# PracticalDMX.net
KiCad netlist of a schematic drawn in EAGLE
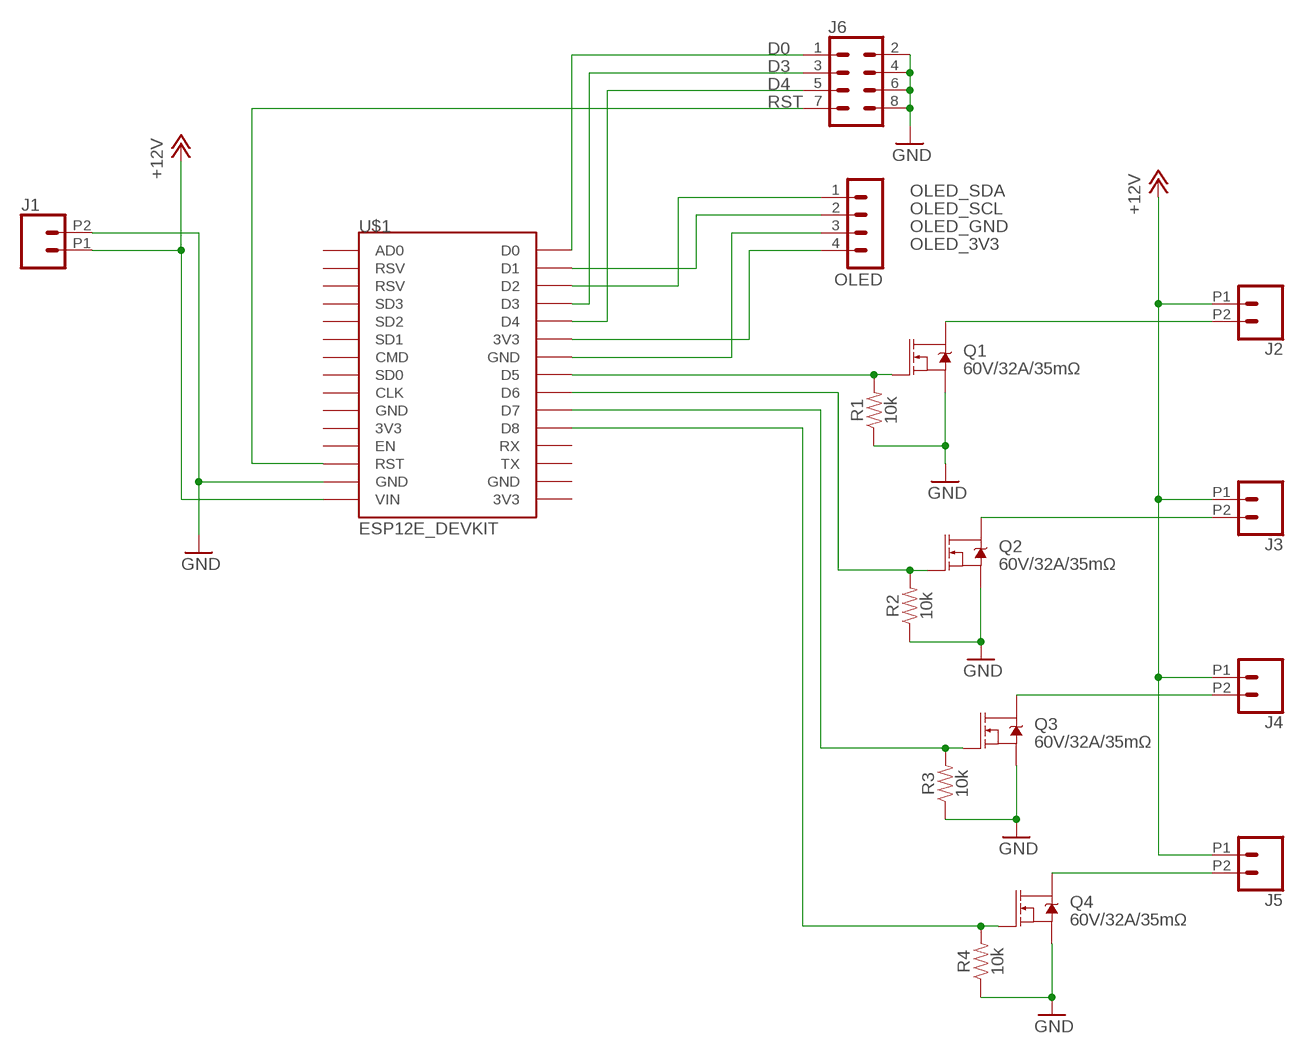
[diagram p0: schematic, sheet 1]

(export (version "E")
  (design (tool "Eeschema 10.0.6"))
  (components
    (comp (ref "J1")
      (value "CONN_022.54MM_SCREWTERM")
      (footprint "eagle-import:1X02_2.54_SCREWTERM")
      (libsource (lib "eagle-import") (part "CONN_022.54MM_SCREWTERM"))
    )
    (comp (ref "J2")
      (value "CONN_022.54MM_SCREWTERM")
      (footprint "eagle-import:1X02_2.54_SCREWTERM")
      (libsource (lib "eagle-import") (part "CONN_022.54MM_SCREWTERM"))
    )
    (comp (ref "J3")
      (value "CONN_022.54MM_SCREWTERM")
      (footprint "eagle-import:1X02_2.54_SCREWTERM")
      (libsource (lib "eagle-import") (part "CONN_022.54MM_SCREWTERM"))
    )
    (comp (ref "J4")
      (value "CONN_022.54MM_SCREWTERM")
      (footprint "eagle-import:1X02_2.54_SCREWTERM")
      (libsource (lib "eagle-import") (part "CONN_022.54MM_SCREWTERM"))
    )
    (comp (ref "J5")
      (value "CONN_022.54MM_SCREWTERM")
      (footprint "eagle-import:1X02_2.54_SCREWTERM")
      (libsource (lib "eagle-import") (part "CONN_022.54MM_SCREWTERM"))
    )
    (comp (ref "J6")
      (value "CONN_04X2")
      (footprint "eagle-import:2X4")
      (libsource (lib "eagle-import") (part "CONN_04X2"))
    )
    (comp (ref "OLED")
      (value "MA04-1")
      (footprint "eagle-import:MA04-1")
      (libsource (lib "eagle-import") (part "MA04-1"))
    )
    (comp (ref "Q1")
      (value "60V/32A/35mΩ")
      (footprint "eagle-import:TO220V")
      (libsource (lib "eagle-import") (part "MOSFET-NCH-FQP30N06L"))
    )
    (comp (ref "Q2")
      (value "60V/32A/35mΩ")
      (footprint "eagle-import:TO220V")
      (libsource (lib "eagle-import") (part "MOSFET-NCH-FQP30N06L"))
    )
    (comp (ref "Q3")
      (value "60V/32A/35mΩ")
      (footprint "eagle-import:TO220V")
      (libsource (lib "eagle-import") (part "MOSFET-NCH-FQP30N06L"))
    )
    (comp (ref "Q4")
      (value "60V/32A/35mΩ")
      (footprint "eagle-import:TO220V")
      (libsource (lib "eagle-import") (part "MOSFET-NCH-FQP30N06L"))
    )
    (comp (ref "R1")
      (value "10k")
      (footprint "eagle-import:AXIAL-0.3")
      (libsource (lib "eagle-import") (part "10KOHM-HORIZ-1/4W-5%"))
    )
    (comp (ref "R2")
      (value "10k")
      (footprint "eagle-import:AXIAL-0.3")
      (libsource (lib "eagle-import") (part "10KOHM-HORIZ-1/4W-5%"))
    )
    (comp (ref "R3")
      (value "10k")
      (footprint "eagle-import:AXIAL-0.3")
      (libsource (lib "eagle-import") (part "10KOHM-HORIZ-1/4W-5%"))
    )
    (comp (ref "R4")
      (value "10k")
      (footprint "eagle-import:AXIAL-0.3")
      (libsource (lib "eagle-import") (part "10KOHM-HORIZ-1/4W-5%"))
    )
    (comp (ref "U$1")
      (value "ESP12E_DEVKIT")
      (footprint "eagle-import:ESP12E_DEVKIT")
      (libsource (lib "eagle-import") (part "ESP12E_DEVKIT"))
    )
  )
  (nets
    (net (code "1") (name "+12V") (class "Default")
      (node (ref "J1") (pin "P1") (pinfunction "1_P1") (pintype "passive"))
      (node (ref "J2") (pin "P1") (pinfunction "1_P1") (pintype "passive"))
      (node (ref "J3") (pin "P1") (pinfunction "1_P1") (pintype "passive"))
      (node (ref "J4") (pin "P1") (pinfunction "1_P1") (pintype "passive"))
      (node (ref "J5") (pin "P1") (pinfunction "1_P1") (pintype "passive"))
      (node (ref "U$1") (pin "VIN") (pinfunction "VIN_VIN") (pintype "bidirectional"))
    )
    (net (code "2") (name "/D0") (class "Default")
      (node (ref "J6") (pin "1") (pinfunction "1_1") (pintype "passive"))
      (node (ref "U$1") (pin "D0") (pinfunction "D0_D0") (pintype "bidirectional"))
    )
    (net (code "3") (name "/D3") (class "Default")
      (node (ref "J6") (pin "3") (pinfunction "3_3") (pintype "passive"))
      (node (ref "U$1") (pin "D3") (pinfunction "D3_D3") (pintype "bidirectional"))
    )
    (net (code "4") (name "/D4") (class "Default")
      (node (ref "J6") (pin "5") (pinfunction "5_5") (pintype "passive"))
      (node (ref "U$1") (pin "D4") (pinfunction "D4_D4") (pintype "bidirectional"))
    )
    (net (code "5") (name "/OLED_3V3") (class "Default")
      (node (ref "OLED") (pin "4") (pinfunction "4_4") (pintype "passive"))
      (node (ref "U$1") (pin "3V3@1") (pinfunction "3V3_3V3@1") (pintype "bidirectional"))
    )
    (net (code "6") (name "/OLED_GND") (class "Default")
      (node (ref "OLED") (pin "3") (pinfunction "3_3") (pintype "passive"))
      (node (ref "U$1") (pin "GND@2") (pinfunction "GND_GND@2") (pintype "bidirectional"))
    )
    (net (code "7") (name "/OLED_SCL") (class "Default")
      (node (ref "OLED") (pin "2") (pinfunction "2_2") (pintype "passive"))
      (node (ref "U$1") (pin "D1") (pinfunction "D1_D1") (pintype "bidirectional"))
    )
    (net (code "8") (name "/OLED_SDA") (class "Default")
      (node (ref "OLED") (pin "1") (pinfunction "1_1") (pintype "passive"))
      (node (ref "U$1") (pin "D2") (pinfunction "D2_D2") (pintype "bidirectional"))
    )
    (net (code "9") (name "/RST") (class "Default")
      (node (ref "J6") (pin "7") (pinfunction "7_7") (pintype "passive"))
      (node (ref "U$1") (pin "RST") (pinfunction "RST_RST") (pintype "bidirectional"))
    )
    (net (code "10") (name "GND") (class "Default")
      (node (ref "J1") (pin "P2") (pinfunction "2_P2") (pintype "passive"))
      (node (ref "J6") (pin "2") (pinfunction "2_2") (pintype "passive"))
      (node (ref "J6") (pin "4") (pinfunction "4_4") (pintype "passive"))
      (node (ref "J6") (pin "6") (pinfunction "6_6") (pintype "passive"))
      (node (ref "J6") (pin "8") (pinfunction "8_8") (pintype "passive"))
      (node (ref "Q1") (pin "3") (pinfunction "S_3") (pintype "bidirectional"))
      (node (ref "Q2") (pin "3") (pinfunction "S_3") (pintype "bidirectional"))
      (node (ref "Q3") (pin "3") (pinfunction "S_3") (pintype "bidirectional"))
      (node (ref "Q4") (pin "3") (pinfunction "S_3") (pintype "bidirectional"))
      (node (ref "R1") (pin "P$1") (pinfunction "1_P$1") (pintype "passive"))
      (node (ref "R2") (pin "P$1") (pinfunction "1_P$1") (pintype "passive"))
      (node (ref "R3") (pin "P$1") (pinfunction "1_P$1") (pintype "passive"))
      (node (ref "R4") (pin "P$1") (pinfunction "1_P$1") (pintype "passive"))
      (node (ref "U$1") (pin "GND@1") (pinfunction "GND_GND@1") (pintype "bidirectional"))
    )
    (net (code "11") (name "Net-(J2-2)") (class "Default")
      (node (ref "J2") (pin "P2") (pinfunction "2_P2") (pintype "passive"))
      (node (ref "Q1") (pin "2") (pinfunction "D_2") (pintype "bidirectional"))
    )
    (net (code "12") (name "Net-(J3-2)") (class "Default")
      (node (ref "J3") (pin "P2") (pinfunction "2_P2") (pintype "passive"))
      (node (ref "Q2") (pin "2") (pinfunction "D_2") (pintype "bidirectional"))
    )
    (net (code "13") (name "Net-(J4-2)") (class "Default")
      (node (ref "J4") (pin "P2") (pinfunction "2_P2") (pintype "passive"))
      (node (ref "Q3") (pin "2") (pinfunction "D_2") (pintype "bidirectional"))
    )
    (net (code "14") (name "Net-(J5-2)") (class "Default")
      (node (ref "J5") (pin "P2") (pinfunction "2_P2") (pintype "passive"))
      (node (ref "Q4") (pin "2") (pinfunction "D_2") (pintype "bidirectional"))
    )
    (net (code "15") (name "Net-(Q1-G)") (class "Default")
      (node (ref "Q1") (pin "1") (pinfunction "G_1") (pintype "bidirectional"))
      (node (ref "R1") (pin "P$2") (pinfunction "2_P$2") (pintype "passive"))
      (node (ref "U$1") (pin "D5") (pinfunction "D5_D5") (pintype "bidirectional"))
    )
    (net (code "16") (name "Net-(Q2-G)") (class "Default")
      (node (ref "Q2") (pin "1") (pinfunction "G_1") (pintype "bidirectional"))
      (node (ref "R2") (pin "P$2") (pinfunction "2_P$2") (pintype "passive"))
      (node (ref "U$1") (pin "D6") (pinfunction "D6_D6") (pintype "bidirectional"))
    )
    (net (code "17") (name "Net-(Q3-G)") (class "Default")
      (node (ref "Q3") (pin "1") (pinfunction "G_1") (pintype "bidirectional"))
      (node (ref "R3") (pin "P$2") (pinfunction "2_P$2") (pintype "passive"))
      (node (ref "U$1") (pin "D7") (pinfunction "D7_D7") (pintype "bidirectional"))
    )
    (net (code "18") (name "Net-(Q4-G)") (class "Default")
      (node (ref "Q4") (pin "1") (pinfunction "G_1") (pintype "bidirectional"))
      (node (ref "R4") (pin "P$2") (pinfunction "2_P$2") (pintype "passive"))
      (node (ref "U$1") (pin "D8") (pinfunction "D8_D8") (pintype "bidirectional"))
    )
    (net (code "19") (name "unconnected-(U$1-3V3-Pad3V3@0)") (class "Default")
      (node (ref "U$1") (pin "3V3@0") (pinfunction "3V3_3V3@0") (pintype "bidirectional"))
    )
    (net (code "20") (name "unconnected-(U$1-3V3-Pad3V3@2)") (class "Default")
      (node (ref "U$1") (pin "3V3@2") (pinfunction "3V3_3V3@2") (pintype "bidirectional"))
    )
    (net (code "21") (name "unconnected-(U$1-GND-PadGND@0)") (class "Default")
      (node (ref "U$1") (pin "GND@0") (pinfunction "GND_GND@0") (pintype "bidirectional"))
    )
    (net (code "22") (name "unconnected-(U$1-GND-PadGND@3)") (class "Default")
      (node (ref "U$1") (pin "GND@3") (pinfunction "GND_GND@3") (pintype "bidirectional"))
    )
    (net (code "23") (name "unconnected-(U$1-PadAD0)") (class "Default")
      (node (ref "U$1") (pin "AD0") (pinfunction "AD0_AD0") (pintype "bidirectional"))
    )
    (net (code "24") (name "unconnected-(U$1-PadCLK)") (class "Default")
      (node (ref "U$1") (pin "CLK") (pinfunction "CLK_CLK") (pintype "bidirectional"))
    )
    (net (code "25") (name "unconnected-(U$1-PadCMD)") (class "Default")
      (node (ref "U$1") (pin "CMD") (pinfunction "CMD_CMD") (pintype "bidirectional"))
    )
    (net (code "26") (name "unconnected-(U$1-PadEN)") (class "Default")
      (node (ref "U$1") (pin "EN") (pinfunction "EN_EN") (pintype "bidirectional"))
    )
    (net (code "27") (name "unconnected-(U$1-PadRX)") (class "Default")
      (node (ref "U$1") (pin "RX") (pinfunction "RX_RX") (pintype "bidirectional"))
    )
    (net (code "28") (name "unconnected-(U$1-PadSD0)") (class "Default")
      (node (ref "U$1") (pin "SD0") (pinfunction "SD0_SD0") (pintype "bidirectional"))
    )
    (net (code "29") (name "unconnected-(U$1-PadSD1)") (class "Default")
      (node (ref "U$1") (pin "SD1") (pinfunction "SD1_SD1") (pintype "bidirectional"))
    )
    (net (code "30") (name "unconnected-(U$1-PadSD2)") (class "Default")
      (node (ref "U$1") (pin "SD2") (pinfunction "SD2_SD2") (pintype "bidirectional"))
    )
    (net (code "31") (name "unconnected-(U$1-PadSD3)") (class "Default")
      (node (ref "U$1") (pin "SD3") (pinfunction "SD3_SD3") (pintype "bidirectional"))
    )
    (net (code "32") (name "unconnected-(U$1-PadTX)") (class "Default")
      (node (ref "U$1") (pin "TX") (pinfunction "TX_TX") (pintype "bidirectional"))
    )
    (net (code "33") (name "unconnected-(U$1-RSV-PadRSV@0)") (class "Default")
      (node (ref "U$1") (pin "RSV@0") (pinfunction "RSV_RSV@0") (pintype "bidirectional"))
    )
    (net (code "34") (name "unconnected-(U$1-RSV-PadRSV@1)") (class "Default")
      (node (ref "U$1") (pin "RSV@1") (pinfunction "RSV_RSV@1") (pintype "bidirectional"))
    )
  )
)
